# mbed.net
KiCad netlist of a schematic drawn in EAGLE
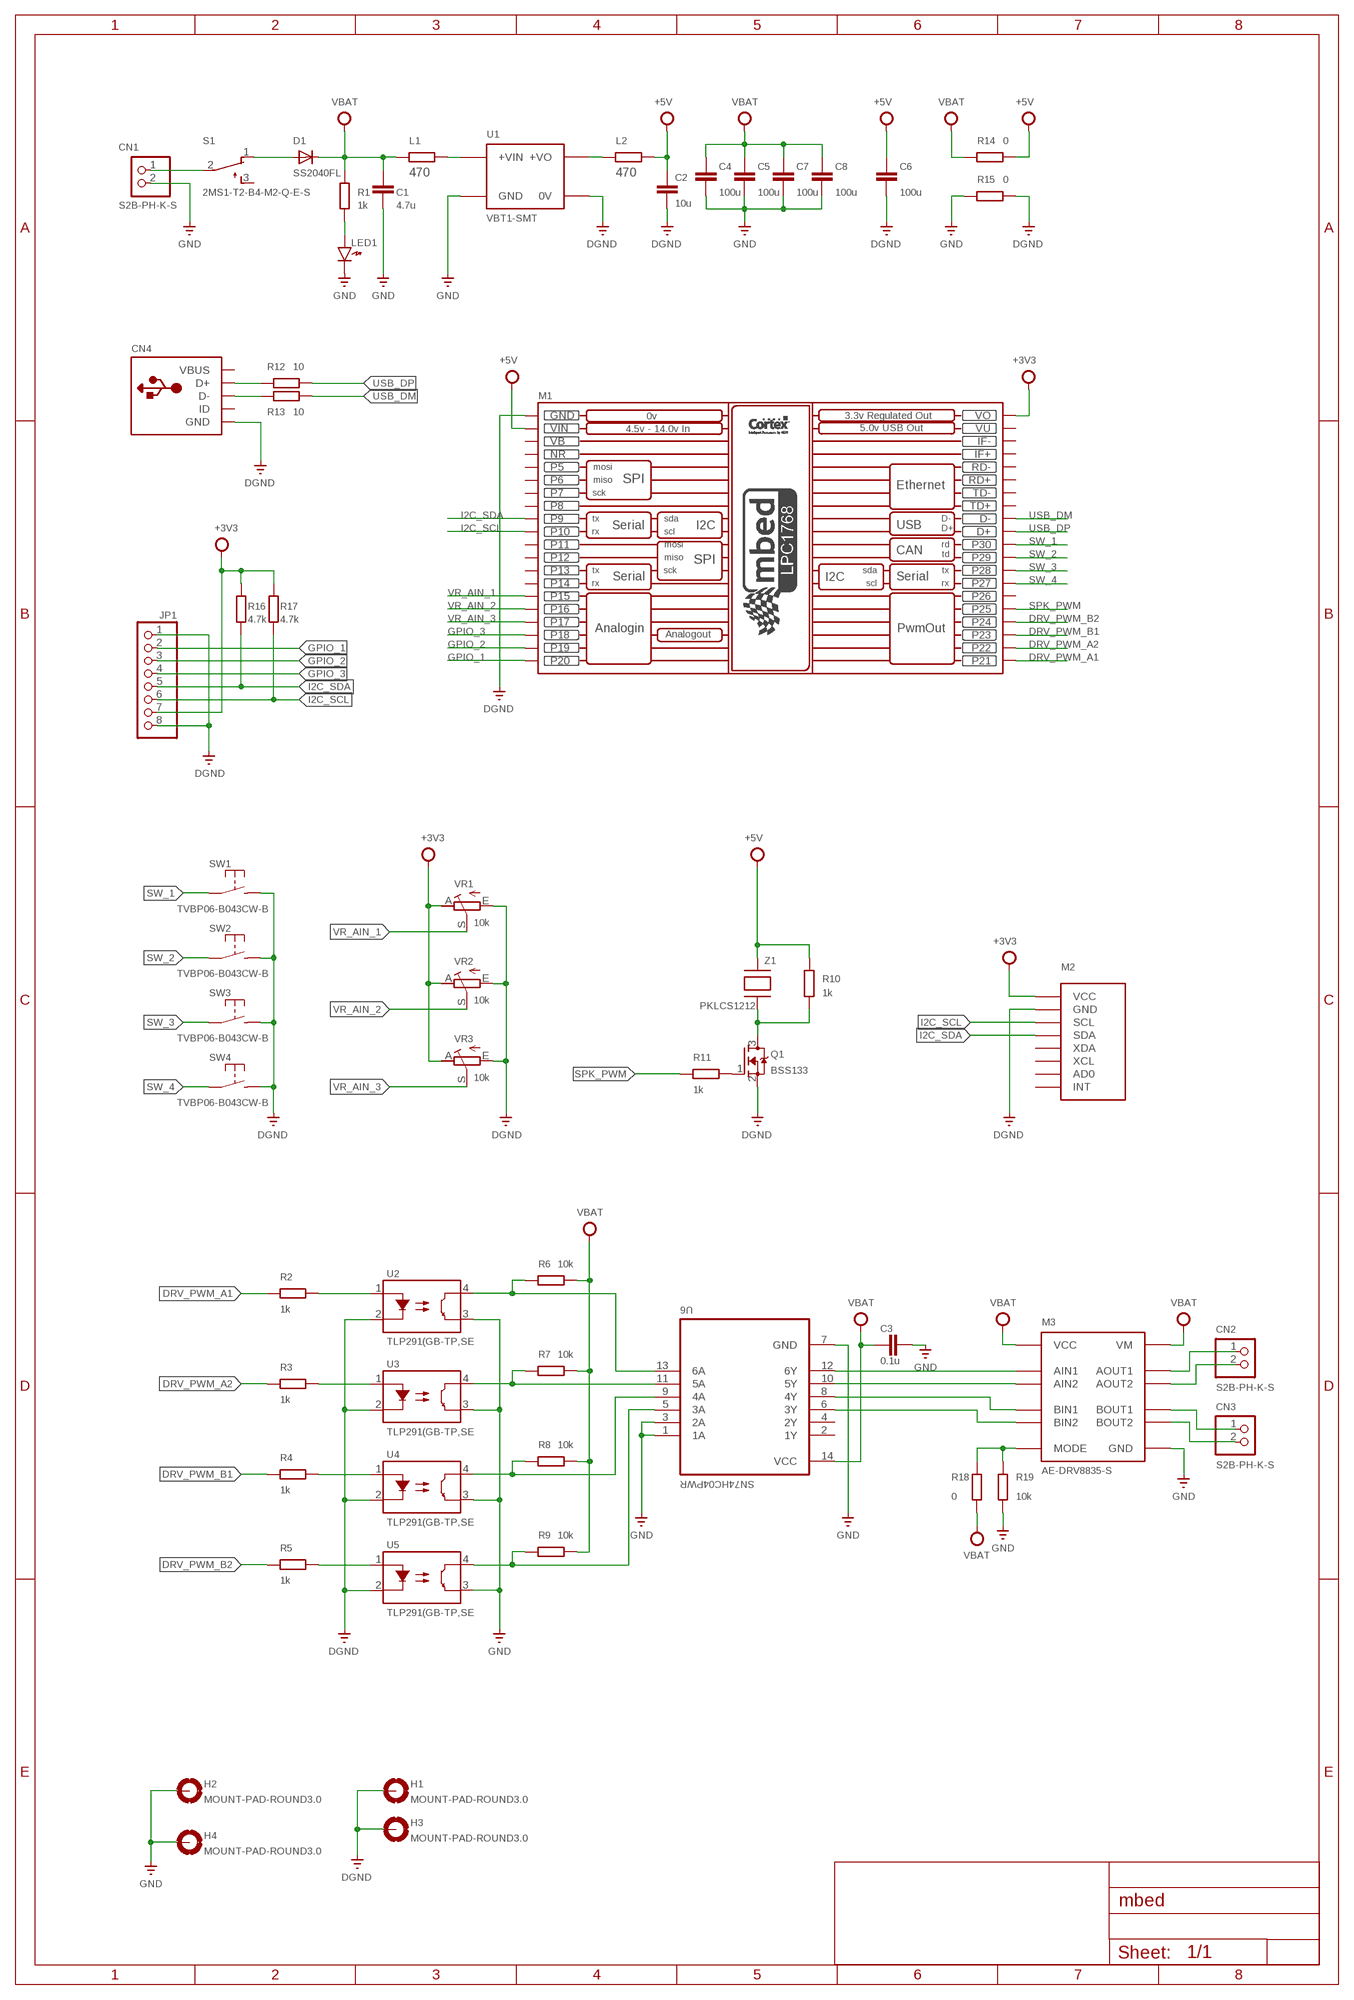
[diagram p0: schematic, sheet 1]

(export (version "E")
  (design (tool "Eeschema 10.0.6"))
  (components
    (comp (ref "C1")
      (value "4.7u")
      (footprint "eagle-import:C0603K")
      (libsource (lib "eagle-import") (part "C-EUC0603K"))
    )
    (comp (ref "C2")
      (value "10u")
      (footprint "eagle-import:C0603K")
      (libsource (lib "eagle-import") (part "C-EUC0603K"))
    )
    (comp (ref "C3")
      (value "0.1u")
      (footprint "eagle-import:C0603K")
      (libsource (lib "eagle-import") (part "C-EUC0603K"))
    )
    (comp (ref "C4")
      (value "100u")
      (footprint "eagle-import:C1206K")
      (libsource (lib "eagle-import") (part "C-EUC1206K"))
    )
    (comp (ref "C5")
      (value "100u")
      (footprint "eagle-import:C1206K")
      (libsource (lib "eagle-import") (part "C-EUC1206K"))
    )
    (comp (ref "C6")
      (value "100u")
      (footprint "eagle-import:C1206K")
      (libsource (lib "eagle-import") (part "C-EUC1206K"))
    )
    (comp (ref "C7")
      (value "100u")
      (footprint "eagle-import:C1206K")
      (libsource (lib "eagle-import") (part "C-EUC1206K"))
    )
    (comp (ref "C8")
      (value "100u")
      (footprint "eagle-import:C1206K")
      (libsource (lib "eagle-import") (part "C-EUC1206K"))
    )
    (comp (ref "CN1")
      (value "S2B-PH-K-S")
      (footprint "eagle-import:JST-PH-2-THM-RA")
      (libsource (lib "eagle-import") (part "JST_2PIN-THM-RA"))
    )
    (comp (ref "CN2")
      (value "S2B-PH-K-S")
      (footprint "eagle-import:JST-PH-2-THM-RA")
      (libsource (lib "eagle-import") (part "JST_2PIN-THM-RA"))
    )
    (comp (ref "CN3")
      (value "S2B-PH-K-S")
      (footprint "eagle-import:JST-PH-2-THM-RA")
      (libsource (lib "eagle-import") (part "JST_2PIN-THM-RA"))
    )
    (comp (ref "CN4")
      (value "USBMINIB")
      (footprint "eagle-import:USB-MINIB")
      (libsource (lib "eagle-import") (part "USBMINIB"))
    )
    (comp (ref "D1")
      (value "SS2040FL")
      (footprint "eagle-import:SOD-123")
      (libsource (lib "eagle-import") (part "DIODESOD-123"))
    )
    (comp (ref "H1")
      (value "MOUNT-PAD-ROUND3.0")
      (footprint "eagle-import:3,0-PAD")
      (libsource (lib "eagle-import") (part "MOUNT-PAD-ROUND3.0"))
    )
    (comp (ref "H2")
      (value "MOUNT-PAD-ROUND3.0")
      (footprint "eagle-import:3,0-PAD")
      (libsource (lib "eagle-import") (part "MOUNT-PAD-ROUND3.0"))
    )
    (comp (ref "H3")
      (value "MOUNT-PAD-ROUND3.0")
      (footprint "eagle-import:3,0-PAD")
      (libsource (lib "eagle-import") (part "MOUNT-PAD-ROUND3.0"))
    )
    (comp (ref "H4")
      (value "MOUNT-PAD-ROUND3.0")
      (footprint "eagle-import:3,0-PAD")
      (libsource (lib "eagle-import") (part "MOUNT-PAD-ROUND3.0"))
    )
    (comp (ref "JP1")
      (value "PINHD-1X8BIG")
      (footprint "eagle-import:1X08-BIG")
      (libsource (lib "eagle-import") (part "PINHD-1X8BIG"))
    )
    (comp (ref "L1")
      (value "470")
      (footprint "eagle-import:R0603")
      (libsource (lib "eagle-import") (part "R-EU_R0603"))
    )
    (comp (ref "L2")
      (value "470")
      (footprint "eagle-import:R0603")
      (libsource (lib "eagle-import") (part "R-EU_R0603"))
    )
    (comp (ref "LED1")
      (value "LED_1608")
      (footprint "eagle-import:LED_1608")
      (libsource (lib "eagle-import") (part "LED_1608"))
    )
    (comp (ref "M1")
      (value "MBED_NXP_LPC1768")
      (footprint "eagle-import:MBED-KIT")
      (libsource (lib "eagle-import") (part "MBED_NXP_LPC1768"))
    )
    (comp (ref "M2")
      (value "MPU6050(GY-521)")
      (footprint "eagle-import:MPU6050")
      (libsource (lib "eagle-import") (part "MPU6050(GY-521)"))
    )
    (comp (ref "M3")
      (value "AE-DRV8835-S")
      (footprint "eagle-import:DIL12")
      (libsource (lib "eagle-import") (part "AE-DRV8835-S"))
    )
    (comp (ref "Q1")
      (value "BSS133")
      (footprint "eagle-import:SOT23")
      (libsource (lib "eagle-import") (part "MOSFET-NREFLOW"))
    )
    (comp (ref "R1")
      (value "1k")
      (footprint "eagle-import:R0603")
      (libsource (lib "eagle-import") (part "R-EU_R0603"))
    )
    (comp (ref "R2")
      (value "1k")
      (footprint "eagle-import:R0603")
      (libsource (lib "eagle-import") (part "R-EU_R0603"))
    )
    (comp (ref "R3")
      (value "1k")
      (footprint "eagle-import:R0603")
      (libsource (lib "eagle-import") (part "R-EU_R0603"))
    )
    (comp (ref "R4")
      (value "1k")
      (footprint "eagle-import:R0603")
      (libsource (lib "eagle-import") (part "R-EU_R0603"))
    )
    (comp (ref "R5")
      (value "1k")
      (footprint "eagle-import:R0603")
      (libsource (lib "eagle-import") (part "R-EU_R0603"))
    )
    (comp (ref "R6")
      (value "10k")
      (footprint "eagle-import:R0603")
      (libsource (lib "eagle-import") (part "R-EU_R0603"))
    )
    (comp (ref "R7")
      (value "10k")
      (footprint "eagle-import:R0603")
      (libsource (lib "eagle-import") (part "R-EU_R0603"))
    )
    (comp (ref "R8")
      (value "10k")
      (footprint "eagle-import:R0603")
      (libsource (lib "eagle-import") (part "R-EU_R0603"))
    )
    (comp (ref "R9")
      (value "10k")
      (footprint "eagle-import:R0603")
      (libsource (lib "eagle-import") (part "R-EU_R0603"))
    )
    (comp (ref "R10")
      (value "1k")
      (footprint "eagle-import:R0603")
      (libsource (lib "eagle-import") (part "R-EU_R0603"))
    )
    (comp (ref "R11")
      (value "1k")
      (footprint "eagle-import:R0603")
      (libsource (lib "eagle-import") (part "R-EU_R0603"))
    )
    (comp (ref "R12")
      (value "10")
      (footprint "eagle-import:R0603")
      (libsource (lib "eagle-import") (part "R-EU_R0603"))
    )
    (comp (ref "R13")
      (value "10")
      (footprint "eagle-import:R0603")
      (libsource (lib "eagle-import") (part "R-EU_R0603"))
    )
    (comp (ref "R14")
      (value "0")
      (footprint "eagle-import:R0603")
      (libsource (lib "eagle-import") (part "R-EU_R0603"))
    )
    (comp (ref "R15")
      (value "0")
      (footprint "eagle-import:R0603")
      (libsource (lib "eagle-import") (part "R-EU_R0603"))
    )
    (comp (ref "R16")
      (value "4.7k")
      (footprint "eagle-import:R0603")
      (libsource (lib "eagle-import") (part "R-EU_R0603"))
    )
    (comp (ref "R17")
      (value "4.7k")
      (footprint "eagle-import:R0603")
      (libsource (lib "eagle-import") (part "R-EU_R0603"))
    )
    (comp (ref "R18")
      (value "0")
      (footprint "eagle-import:R0603")
      (libsource (lib "eagle-import") (part "R-EU_R0603"))
    )
    (comp (ref "R19")
      (value "10k")
      (footprint "eagle-import:R0603")
      (libsource (lib "eagle-import") (part "R-EU_R0603"))
    )
    (comp (ref "S1")
      (value "2MS1-T2-B4-M2-Q-E-S")
      (footprint "eagle-import:TL3XPO")
      (libsource (lib "eagle-import") (part "TL32PO"))
    )
    (comp (ref "SW1")
      (value "TVBP06-B043CW-B")
      (footprint "eagle-import:SW1")
      (libsource (lib "eagle-import") (part "TUCT_SW_MINI"))
    )
    (comp (ref "SW2")
      (value "TVBP06-B043CW-B")
      (footprint "eagle-import:SW1")
      (libsource (lib "eagle-import") (part "TUCT_SW_MINI"))
    )
    (comp (ref "SW3")
      (value "TVBP06-B043CW-B")
      (footprint "eagle-import:SW1")
      (libsource (lib "eagle-import") (part "TUCT_SW_MINI"))
    )
    (comp (ref "SW4")
      (value "TVBP06-B043CW-B")
      (footprint "eagle-import:SW1")
      (libsource (lib "eagle-import") (part "TUCT_SW_MINI"))
    )
    (comp (ref "U1")
      (value "VBT1-SMT")
      (footprint "eagle-import:VBT1-SMT")
      (libsource (lib "eagle-import") (part "VBT1-SMT"))
    )
    (comp (ref "U2")
      (value "TLP291(GB-TP,SE")
      (footprint "eagle-import:SOIC127P700X220-4N")
      (fields (field (name "MF") "Toshiba Semiconductor"))
      (libsource (lib "eagle-import") (part "TLP291(GB-TP,SE"))
    )
    (comp (ref "U3")
      (value "TLP291(GB-TP,SE")
      (footprint "eagle-import:SOIC127P700X220-4N")
      (fields (field (name "MF") "Toshiba Semiconductor"))
      (libsource (lib "eagle-import") (part "TLP291(GB-TP,SE"))
    )
    (comp (ref "U4")
      (value "TLP291(GB-TP,SE")
      (footprint "eagle-import:SOIC127P700X220-4N")
      (fields (field (name "MF") "Toshiba Semiconductor"))
      (libsource (lib "eagle-import") (part "TLP291(GB-TP,SE"))
    )
    (comp (ref "U5")
      (value "TLP291(GB-TP,SE")
      (footprint "eagle-import:SOIC127P700X220-4N")
      (fields (field (name "MF") "Toshiba Semiconductor"))
      (libsource (lib "eagle-import") (part "TLP291(GB-TP,SE"))
    )
    (comp (ref "U6")
      (value "SN74HC04PWR")
      (footprint "eagle-import:SOP65P640X120-14N")
      (libsource (lib "eagle-import") (part "SN74HC04PW"))
    )
    (comp (ref "VR1")
      (value "10k")
      (footprint "eagle-import:VR-BOURNS")
      (libsource (lib "eagle-import") (part "VR-BOURNS"))
    )
    (comp (ref "VR2")
      (value "10k")
      (footprint "eagle-import:VR-BOURNS")
      (libsource (lib "eagle-import") (part "VR-BOURNS"))
    )
    (comp (ref "VR3")
      (value "10k")
      (footprint "eagle-import:VR-BOURNS")
      (libsource (lib "eagle-import") (part "VR-BOURNS"))
    )
    (comp (ref "Z1")
      (value "PKLCS1212")
      (footprint "eagle-import:PKLCS1212")
      (libsource (lib "eagle-import") (part "PKLCS1212"))
    )
  )
  (nets
    (net (code "1") (name "+3V3") (class "Default")
      (node (ref "JP1") (pin "7") (pinfunction "7_7") (pintype "passive"))
      (node (ref "M1") (pin "VOUT") (pinfunction "VO_VOUT") (pintype "power_in"))
      (node (ref "M2") (pin "P$1") (pinfunction "VCC_P$1") (pintype "bidirectional"))
      (node (ref "R16") (pin "2") (pinfunction "2_2") (pintype "passive"))
      (node (ref "R17") (pin "2") (pinfunction "2_2") (pintype "passive"))
      (node (ref "VR1") (pin "A") (pinfunction "A_A") (pintype "passive"))
      (node (ref "VR2") (pin "A") (pinfunction "A_A") (pintype "passive"))
      (node (ref "VR3") (pin "A") (pinfunction "A_A") (pintype "passive"))
    )
    (net (code "2") (name "+5V") (class "Default")
      (node (ref "C2") (pin "1") (pinfunction "1_1") (pintype "passive"))
      (node (ref "C6") (pin "1") (pinfunction "1_1") (pintype "passive"))
      (node (ref "L2") (pin "2") (pinfunction "2_2") (pintype "passive"))
      (node (ref "M1") (pin "VIN") (pinfunction "VIN_VIN") (pintype "power_in"))
      (node (ref "R10") (pin "2") (pinfunction "2_2") (pintype "passive"))
      (node (ref "R14") (pin "1") (pinfunction "1_1") (pintype "passive"))
      (node (ref "Z1") (pin "P$2") (pinfunction "P$2_P$2") (pintype "bidirectional"))
    )
    (net (code "3") (name "/NR") (class "Default")
      (node (ref "M1") (pin "NR") (pinfunction "NR_NR") (pintype "power_in"))
    )
    (net (code "4") (name "/VB") (class "Default")
      (node (ref "M1") (pin "VB") (pinfunction "VB_VB") (pintype "power_in"))
    )
    (net (code "5") (name "/VBUS") (class "Default")
      (node (ref "CN4") (pin "VBUS") (pinfunction "VBUS_VBUS") (pintype "power_in"))
    )
    (net (code "6") (name "/VU") (class "Default")
      (node (ref "M1") (pin "VU") (pinfunction "VU_VU") (pintype "power_in"))
    )
    (net (code "7") (name "DGND") (class "Default")
      (node (ref "C2") (pin "2") (pinfunction "2_2") (pintype "passive"))
      (node (ref "C6") (pin "2") (pinfunction "2_2") (pintype "passive"))
      (node (ref "CN4") (pin "GND") (pinfunction "GND_GND") (pintype "power_in"))
      (node (ref "H1") (pin "B3,0") (pinfunction "MOUNT_B3,0") (pintype "passive"))
      (node (ref "H3") (pin "B3,0") (pinfunction "MOUNT_B3,0") (pintype "passive"))
      (node (ref "JP1") (pin "1") (pinfunction "1_1") (pintype "passive"))
      (node (ref "JP1") (pin "8") (pinfunction "8_8") (pintype "passive"))
      (node (ref "M1") (pin "GND") (pinfunction "GND_GND") (pintype "power_in"))
      (node (ref "M2") (pin "P$2") (pinfunction "GND_P$2") (pintype "bidirectional"))
      (node (ref "Q1") (pin "2") (pinfunction "S_2") (pintype "bidirectional"))
      (node (ref "R15") (pin "1") (pinfunction "1_1") (pintype "passive"))
      (node (ref "SW1") (pin "P$2") (pinfunction "S_P$2") (pintype "passive"))
      (node (ref "SW2") (pin "P$2") (pinfunction "S_P$2") (pintype "passive"))
      (node (ref "SW3") (pin "P$2") (pinfunction "S_P$2") (pintype "passive"))
      (node (ref "SW4") (pin "P$2") (pinfunction "S_P$2") (pintype "passive"))
      (node (ref "U1") (pin "P$4") (pinfunction "0V_P$4") (pintype "power_in"))
      (node (ref "U2") (pin "2") (pinfunction "C_2") (pintype "passive"))
      (node (ref "U3") (pin "2") (pinfunction "C_2") (pintype "passive"))
      (node (ref "U4") (pin "2") (pinfunction "C_2") (pintype "passive"))
      (node (ref "U5") (pin "2") (pinfunction "C_2") (pintype "passive"))
      (node (ref "VR1") (pin "E") (pinfunction "E_E") (pintype "passive"))
      (node (ref "VR2") (pin "E") (pinfunction "E_E") (pintype "passive"))
      (node (ref "VR3") (pin "E") (pinfunction "E_E") (pintype "passive"))
    )
    (net (code "8") (name "DRV_PWM_A1") (class "Default")
      (node (ref "M1") (pin "P$21") (pinfunction "P21_P$21") (pintype "bidirectional"))
      (node (ref "R2") (pin "2") (pinfunction "2_2") (pintype "passive"))
    )
    (net (code "9") (name "DRV_PWM_A2") (class "Default")
      (node (ref "M1") (pin "P$22") (pinfunction "P22_P$22") (pintype "bidirectional"))
      (node (ref "R3") (pin "2") (pinfunction "2_2") (pintype "passive"))
    )
    (net (code "10") (name "DRV_PWM_B1") (class "Default")
      (node (ref "M1") (pin "P$23") (pinfunction "P23_P$23") (pintype "bidirectional"))
      (node (ref "R4") (pin "2") (pinfunction "2_2") (pintype "passive"))
    )
    (net (code "11") (name "DRV_PWM_B2") (class "Default")
      (node (ref "M1") (pin "P$24") (pinfunction "P24_P$24") (pintype "bidirectional"))
      (node (ref "R5") (pin "2") (pinfunction "2_2") (pintype "passive"))
    )
    (net (code "12") (name "GND") (class "Default")
      (node (ref "C1") (pin "2") (pinfunction "2_2") (pintype "passive"))
      (node (ref "C3") (pin "2") (pinfunction "2_2") (pintype "passive"))
      (node (ref "C4") (pin "2") (pinfunction "2_2") (pintype "passive"))
      (node (ref "C5") (pin "2") (pinfunction "2_2") (pintype "passive"))
      (node (ref "C7") (pin "2") (pinfunction "2_2") (pintype "passive"))
      (node (ref "C8") (pin "2") (pinfunction "2_2") (pintype "passive"))
      (node (ref "CN1") (pin "2") (pinfunction "1_2") (pintype "passive"))
      (node (ref "H2") (pin "B3,0") (pinfunction "MOUNT_B3,0") (pintype "passive"))
      (node (ref "H4") (pin "B3,0") (pinfunction "MOUNT_B3,0") (pintype "passive"))
      (node (ref "LED1") (pin "K") (pinfunction "K_K") (pintype "passive"))
      (node (ref "M3") (pin "P$6") (pinfunction "GND_P$6") (pintype "bidirectional"))
      (node (ref "R15") (pin "2") (pinfunction "2_2") (pintype "passive"))
      (node (ref "R19") (pin "2") (pinfunction "2_2") (pintype "passive"))
      (node (ref "U1") (pin "P$1") (pinfunction "GND_P$1") (pintype "power_in"))
      (node (ref "U2") (pin "3") (pinfunction "EMIT_3") (pintype "passive"))
      (node (ref "U3") (pin "3") (pinfunction "EMIT_3") (pintype "passive"))
      (node (ref "U4") (pin "3") (pinfunction "EMIT_3") (pintype "passive"))
      (node (ref "U5") (pin "3") (pinfunction "EMIT_3") (pintype "passive"))
      (node (ref "U6") (pin "1") (pinfunction "1A_1") (pintype "input"))
      (node (ref "U6") (pin "3") (pinfunction "2A_3") (pintype "input"))
      (node (ref "U6") (pin "7") (pinfunction "GND_7") (pintype "power_in"))
    )
    (net (code "13") (name "GPIO_1") (class "Default")
      (node (ref "JP1") (pin "2") (pinfunction "2_2") (pintype "passive"))
      (node (ref "M1") (pin "P$20") (pinfunction "P20_P$20") (pintype "bidirectional"))
    )
    (net (code "14") (name "GPIO_2") (class "Default")
      (node (ref "JP1") (pin "3") (pinfunction "3_3") (pintype "passive"))
      (node (ref "M1") (pin "P$19") (pinfunction "P19_P$19") (pintype "bidirectional"))
    )
    (net (code "15") (name "GPIO_3") (class "Default")
      (node (ref "JP1") (pin "4") (pinfunction "4_4") (pintype "passive"))
      (node (ref "M1") (pin "P$18") (pinfunction "P18_P$18") (pintype "bidirectional"))
    )
    (net (code "16") (name "I2C_SCL") (class "Default")
      (node (ref "JP1") (pin "6") (pinfunction "6_6") (pintype "passive"))
      (node (ref "M1") (pin "P$10") (pinfunction "P10_P$10") (pintype "bidirectional"))
      (node (ref "M2") (pin "P$3") (pinfunction "SCL_P$3") (pintype "bidirectional"))
      (node (ref "R17") (pin "1") (pinfunction "1_1") (pintype "passive"))
    )
    (net (code "17") (name "I2C_SDA") (class "Default")
      (node (ref "JP1") (pin "5") (pinfunction "5_5") (pintype "passive"))
      (node (ref "M1") (pin "P$9") (pinfunction "P9_P$9") (pintype "bidirectional"))
      (node (ref "M2") (pin "P$4") (pinfunction "SDA_P$4") (pintype "bidirectional"))
      (node (ref "R16") (pin "1") (pinfunction "1_1") (pintype "passive"))
    )
    (net (code "18") (name "Net-(CN1-2)") (class "Default")
      (node (ref "CN1") (pin "1") (pinfunction "2_1") (pintype "passive"))
      (node (ref "S1") (pin "2") (pinfunction "P_2") (pintype "passive"))
    )
    (net (code "19") (name "Net-(CN2-1)") (class "Default")
      (node (ref "CN2") (pin "2") (pinfunction "1_2") (pintype "passive"))
      (node (ref "M3") (pin "P$3") (pinfunction "AOUT2_P$3") (pintype "bidirectional"))
    )
    (net (code "20") (name "Net-(CN2-2)") (class "Default")
      (node (ref "CN2") (pin "1") (pinfunction "2_1") (pintype "passive"))
      (node (ref "M3") (pin "P$2") (pinfunction "AOUT1_P$2") (pintype "bidirectional"))
    )
    (net (code "21") (name "Net-(CN3-1)") (class "Default")
      (node (ref "CN3") (pin "2") (pinfunction "1_2") (pintype "passive"))
      (node (ref "M3") (pin "P$5") (pinfunction "BOUT2_P$5") (pintype "bidirectional"))
    )
    (net (code "22") (name "Net-(CN3-2)") (class "Default")
      (node (ref "CN3") (pin "1") (pinfunction "2_1") (pintype "passive"))
      (node (ref "M3") (pin "P$4") (pinfunction "BOUT1_P$4") (pintype "bidirectional"))
    )
    (net (code "23") (name "Net-(CN4-PadD+)") (class "Default")
      (node (ref "CN4") (pin "D+") (pinfunction "D+_D+") (pintype "bidirectional"))
      (node (ref "R12") (pin "1") (pinfunction "1_1") (pintype "passive"))
    )
    (net (code "24") (name "Net-(CN4-PadD-)") (class "Default")
      (node (ref "CN4") (pin "D-") (pinfunction "D-_D-") (pintype "bidirectional"))
      (node (ref "R13") (pin "1") (pinfunction "1_1") (pintype "passive"))
    )
    (net (code "25") (name "Net-(LED1-PadA)") (class "Default")
      (node (ref "LED1") (pin "A") (pinfunction "A_A") (pintype "passive"))
      (node (ref "R1") (pin "1") (pinfunction "1_1") (pintype "passive"))
    )
    (net (code "26") (name "Net-(M3-AIN1)") (class "Default")
      (node (ref "M3") (pin "P$10") (pinfunction "AIN1_P$10") (pintype "bidirectional"))
      (node (ref "U6") (pin "12") (pinfunction "6Y_12") (pintype "output"))
    )
    (net (code "27") (name "Net-(M3-AIN2)") (class "Default")
      (node (ref "M3") (pin "P$9") (pinfunction "AIN2_P$9") (pintype "bidirectional"))
      (node (ref "U6") (pin "10") (pinfunction "5Y_10") (pintype "output"))
    )
    (net (code "28") (name "Net-(M3-BIN1)") (class "Default")
      (node (ref "M3") (pin "P$8") (pinfunction "BIN1_P$8") (pintype "bidirectional"))
      (node (ref "U6") (pin "8") (pinfunction "4Y_8") (pintype "output"))
    )
    (net (code "29") (name "Net-(M3-BIN2)") (class "Default")
      (node (ref "M3") (pin "P$7") (pinfunction "BIN2_P$7") (pintype "bidirectional"))
      (node (ref "U6") (pin "6") (pinfunction "3Y_6") (pintype "output"))
    )
    (net (code "30") (name "Net-(M3-MODE)") (class "Default")
      (node (ref "M3") (pin "P$11") (pinfunction "MODE_P$11") (pintype "bidirectional"))
      (node (ref "R18") (pin "1") (pinfunction "1_1") (pintype "passive"))
      (node (ref "R19") (pin "1") (pinfunction "1_1") (pintype "passive"))
    )
    (net (code "31") (name "Net-(Q1-D)") (class "Default")
      (node (ref "Q1") (pin "3") (pinfunction "D_3") (pintype "bidirectional"))
      (node (ref "R10") (pin "1") (pinfunction "1_1") (pintype "passive"))
      (node (ref "Z1") (pin "P$1") (pinfunction "P$1_P$1") (pintype "bidirectional"))
    )
    (net (code "32") (name "Net-(Q1-G)") (class "Default")
      (node (ref "Q1") (pin "1") (pinfunction "G_1") (pintype "bidirectional"))
      (node (ref "R11") (pin "1") (pinfunction "1_1") (pintype "passive"))
    )
    (net (code "33") (name "Net-(S1-O)") (class "Default")
      (node (ref "D1") (pin "A") (pinfunction "A_A") (pintype "passive"))
      (node (ref "S1") (pin "1") (pinfunction "O_1") (pintype "passive"))
    )
    (net (code "34") (name "Net-(U1-+VIN)") (class "Default")
      (node (ref "L1") (pin "2") (pinfunction "2_2") (pintype "passive"))
      (node (ref "U1") (pin "P$2") (pinfunction "+VIN_P$2") (pintype "power_in"))
    )
    (net (code "35") (name "Net-(U1-+VO)") (class "Default")
      (node (ref "L2") (pin "1") (pinfunction "1_1") (pintype "passive"))
      (node (ref "U1") (pin "P$5") (pinfunction "+VO_P$5") (pintype "power_in"))
    )
    (net (code "36") (name "Net-(U2-A)") (class "Default")
      (node (ref "R2") (pin "1") (pinfunction "1_1") (pintype "passive"))
      (node (ref "U2") (pin "1") (pinfunction "A_1") (pintype "passive"))
    )
    (net (code "37") (name "Net-(U2-COL)") (class "Default")
      (node (ref "R6") (pin "1") (pinfunction "1_1") (pintype "passive"))
      (node (ref "U2") (pin "4") (pinfunction "COL_4") (pintype "passive"))
      (node (ref "U6") (pin "13") (pinfunction "6A_13") (pintype "input"))
    )
    (net (code "38") (name "Net-(U3-A)") (class "Default")
      (node (ref "R3") (pin "1") (pinfunction "1_1") (pintype "passive"))
      (node (ref "U3") (pin "1") (pinfunction "A_1") (pintype "passive"))
    )
    (net (code "39") (name "Net-(U3-COL)") (class "Default")
      (node (ref "R7") (pin "1") (pinfunction "1_1") (pintype "passive"))
      (node (ref "U3") (pin "4") (pinfunction "COL_4") (pintype "passive"))
      (node (ref "U6") (pin "11") (pinfunction "5A_11") (pintype "input"))
    )
    (net (code "40") (name "Net-(U4-A)") (class "Default")
      (node (ref "R4") (pin "1") (pinfunction "1_1") (pintype "passive"))
      (node (ref "U4") (pin "1") (pinfunction "A_1") (pintype "passive"))
    )
    (net (code "41") (name "Net-(U4-COL)") (class "Default")
      (node (ref "R8") (pin "1") (pinfunction "1_1") (pintype "passive"))
      (node (ref "U4") (pin "4") (pinfunction "COL_4") (pintype "passive"))
      (node (ref "U6") (pin "9") (pinfunction "4A_9") (pintype "input"))
    )
    (net (code "42") (name "Net-(U5-A)") (class "Default")
      (node (ref "R5") (pin "1") (pinfunction "1_1") (pintype "passive"))
      (node (ref "U5") (pin "1") (pinfunction "A_1") (pintype "passive"))
    )
    (net (code "43") (name "Net-(U5-COL)") (class "Default")
      (node (ref "R9") (pin "2") (pinfunction "2_2") (pintype "passive"))
      (node (ref "U5") (pin "4") (pinfunction "COL_4") (pintype "passive"))
      (node (ref "U6") (pin "5") (pinfunction "3A_5") (pintype "input"))
    )
    (net (code "44") (name "SPK_PWM") (class "Default")
      (node (ref "M1") (pin "P$25") (pinfunction "P25_P$25") (pintype "bidirectional"))
      (node (ref "R11") (pin "2") (pinfunction "2_2") (pintype "passive"))
    )
    (net (code "45") (name "SW_1") (class "Default")
      (node (ref "M1") (pin "P$30") (pinfunction "P30_P$30") (pintype "bidirectional"))
      (node (ref "SW1") (pin "P$1") (pinfunction "P_P$1") (pintype "passive"))
    )
    (net (code "46") (name "SW_2") (class "Default")
      (node (ref "M1") (pin "P$29") (pinfunction "P29_P$29") (pintype "bidirectional"))
      (node (ref "SW2") (pin "P$1") (pinfunction "P_P$1") (pintype "passive"))
    )
    (net (code "47") (name "SW_3") (class "Default")
      (node (ref "M1") (pin "P$28") (pinfunction "P28_P$28") (pintype "bidirectional"))
      (node (ref "SW3") (pin "P$1") (pinfunction "P_P$1") (pintype "passive"))
    )
    (net (code "48") (name "SW_4") (class "Default")
      (node (ref "M1") (pin "P$27") (pinfunction "P27_P$27") (pintype "bidirectional"))
      (node (ref "SW4") (pin "P$1") (pinfunction "P_P$1") (pintype "passive"))
    )
    (net (code "49") (name "USB_DM") (class "Default")
      (node (ref "M1") (pin "D-") (pinfunction "D-_D-") (pintype "bidirectional"))
      (node (ref "R13") (pin "2") (pinfunction "2_2") (pintype "passive"))
    )
    (net (code "50") (name "USB_DP") (class "Default")
      (node (ref "M1") (pin "D+") (pinfunction "D+_D+") (pintype "bidirectional"))
      (node (ref "R12") (pin "2") (pinfunction "2_2") (pintype "passive"))
    )
    (net (code "51") (name "VBAT") (class "Default")
      (node (ref "C1") (pin "1") (pinfunction "1_1") (pintype "passive"))
      (node (ref "C3") (pin "1") (pinfunction "1_1") (pintype "passive"))
      (node (ref "C4") (pin "1") (pinfunction "1_1") (pintype "passive"))
      (node (ref "C5") (pin "1") (pinfunction "1_1") (pintype "passive"))
      (node (ref "C7") (pin "1") (pinfunction "1_1") (pintype "passive"))
      (node (ref "C8") (pin "1") (pinfunction "1_1") (pintype "passive"))
      (node (ref "D1") (pin "C") (pinfunction "C_C") (pintype "passive"))
      (node (ref "L1") (pin "1") (pinfunction "1_1") (pintype "passive"))
      (node (ref "M3") (pin "P$1") (pinfunction "VM_P$1") (pintype "bidirectional"))
      (node (ref "M3") (pin "P$12") (pinfunction "VCC_P$12") (pintype "bidirectional"))
      (node (ref "R1") (pin "2") (pinfunction "2_2") (pintype "passive"))
      (node (ref "R14") (pin "2") (pinfunction "2_2") (pintype "passive"))
      (node (ref "R18") (pin "2") (pinfunction "2_2") (pintype "passive"))
      (node (ref "R6") (pin "2") (pinfunction "2_2") (pintype "passive"))
      (node (ref "R7") (pin "2") (pinfunction "2_2") (pintype "passive"))
      (node (ref "R8") (pin "2") (pinfunction "2_2") (pintype "passive"))
      (node (ref "R9") (pin "1") (pinfunction "1_1") (pintype "passive"))
      (node (ref "U6") (pin "14") (pinfunction "VCC_14") (pintype "power_in"))
    )
    (net (code "52") (name "VR_AIN_1") (class "Default")
      (node (ref "M1") (pin "P$15") (pinfunction "P15_P$15") (pintype "bidirectional"))
      (node (ref "VR1") (pin "S") (pinfunction "S_S") (pintype "passive"))
    )
    (net (code "53") (name "VR_AIN_2") (class "Default")
      (node (ref "M1") (pin "P$16") (pinfunction "P16_P$16") (pintype "bidirectional"))
      (node (ref "VR2") (pin "S") (pinfunction "S_S") (pintype "passive"))
    )
    (net (code "54") (name "VR_AIN_3") (class "Default")
      (node (ref "M1") (pin "P$17") (pinfunction "P17_P$17") (pintype "bidirectional"))
      (node (ref "VR3") (pin "S") (pinfunction "S_S") (pintype "passive"))
    )
    (net (code "55") (name "unconnected-(CN4-PadID)") (class "Default")
      (node (ref "CN4") (pin "ID") (pinfunction "ID_ID") (pintype "bidirectional"))
    )
    (net (code "56") (name "unconnected-(M1-P5-PadP$5)") (class "Default")
      (node (ref "M1") (pin "P$5") (pinfunction "P5_P$5") (pintype "bidirectional"))
    )
    (net (code "57") (name "unconnected-(M1-P6-PadP$6)") (class "Default")
      (node (ref "M1") (pin "P$6") (pinfunction "P6_P$6") (pintype "bidirectional"))
    )
    (net (code "58") (name "unconnected-(M1-P7-PadP$7)") (class "Default")
      (node (ref "M1") (pin "P$7") (pinfunction "P7_P$7") (pintype "bidirectional"))
    )
    (net (code "59") (name "unconnected-(M1-P8-PadP$8)") (class "Default")
      (node (ref "M1") (pin "P$8") (pinfunction "P8_P$8") (pintype "bidirectional"))
    )
    (net (code "60") (name "unconnected-(M1-P11-PadP$11)") (class "Default")
      (node (ref "M1") (pin "P$11") (pinfunction "P11_P$11") (pintype "bidirectional"))
    )
    (net (code "61") (name "unconnected-(M1-P12-PadP$12)") (class "Default")
      (node (ref "M1") (pin "P$12") (pinfunction "P12_P$12") (pintype "bidirectional"))
    )
    (net (code "62") (name "unconnected-(M1-P13-PadP$13)") (class "Default")
      (node (ref "M1") (pin "P$13") (pinfunction "P13_P$13") (pintype "bidirectional"))
    )
    (net (code "63") (name "unconnected-(M1-P14-PadP$14)") (class "Default")
      (node (ref "M1") (pin "P$14") (pinfunction "P14_P$14") (pintype "bidirectional"))
    )
    (net (code "64") (name "unconnected-(M1-P26-PadP$26)") (class "Default")
      (node (ref "M1") (pin "P$26") (pinfunction "P26_P$26") (pintype "bidirectional"))
    )
    (net (code "65") (name "unconnected-(M1-PadIF+)") (class "Default")
      (node (ref "M1") (pin "IF+") (pinfunction "IF+_IF+") (pintype "bidirectional"))
    )
    (net (code "66") (name "unconnected-(M1-PadIF-)") (class "Default")
      (node (ref "M1") (pin "IF-") (pinfunction "IF-_IF-") (pintype "bidirectional"))
    )
    (net (code "67") (name "unconnected-(M1-PadRD+)") (class "Default")
      (node (ref "M1") (pin "RD+") (pinfunction "RD+_RD+") (pintype "bidirectional"))
    )
    (net (code "68") (name "unconnected-(M1-PadRD-)") (class "Default")
      (node (ref "M1") (pin "RD-") (pinfunction "RD-_RD-") (pintype "bidirectional"))
    )
    (net (code "69") (name "unconnected-(M1-PadTD+)") (class "Default")
      (node (ref "M1") (pin "TD+") (pinfunction "TD+_TD+") (pintype "bidirectional"))
    )
    (net (code "70") (name "unconnected-(M1-PadTD-)") (class "Default")
      (node (ref "M1") (pin "TD-") (pinfunction "TD-_TD-") (pintype "bidirectional"))
    )
    (net (code "71") (name "unconnected-(M2-AD0-PadP$7)") (class "Default")
      (node (ref "M2") (pin "P$7") (pinfunction "AD0_P$7") (pintype "bidirectional"))
    )
    (net (code "72") (name "unconnected-(M2-INT-PadP$8)") (class "Default")
      (node (ref "M2") (pin "P$8") (pinfunction "INT_P$8") (pintype "bidirectional"))
    )
    (net (code "73") (name "unconnected-(M2-XCL-PadP$6)") (class "Default")
      (node (ref "M2") (pin "P$6") (pinfunction "XCL_P$6") (pintype "bidirectional"))
    )
    (net (code "74") (name "unconnected-(M2-XDA-PadP$5)") (class "Default")
      (node (ref "M2") (pin "P$5") (pinfunction "XDA_P$5") (pintype "bidirectional"))
    )
    (net (code "75") (name "unconnected-(S1-S-Pad3)") (class "Default")
      (node (ref "S1") (pin "3") (pinfunction "S_3") (pintype "passive"))
    )
    (net (code "76") (name "unconnected-(U6-1Y-Pad2)") (class "Default")
      (node (ref "U6") (pin "2") (pinfunction "1Y_2") (pintype "output"))
    )
    (net (code "77") (name "unconnected-(U6-2Y-Pad4)") (class "Default")
      (node (ref "U6") (pin "4") (pinfunction "2Y_4") (pintype "output"))
    )
  )
)
